# connect.net
KiCad netlist of a schematic drawn in Altium Designer
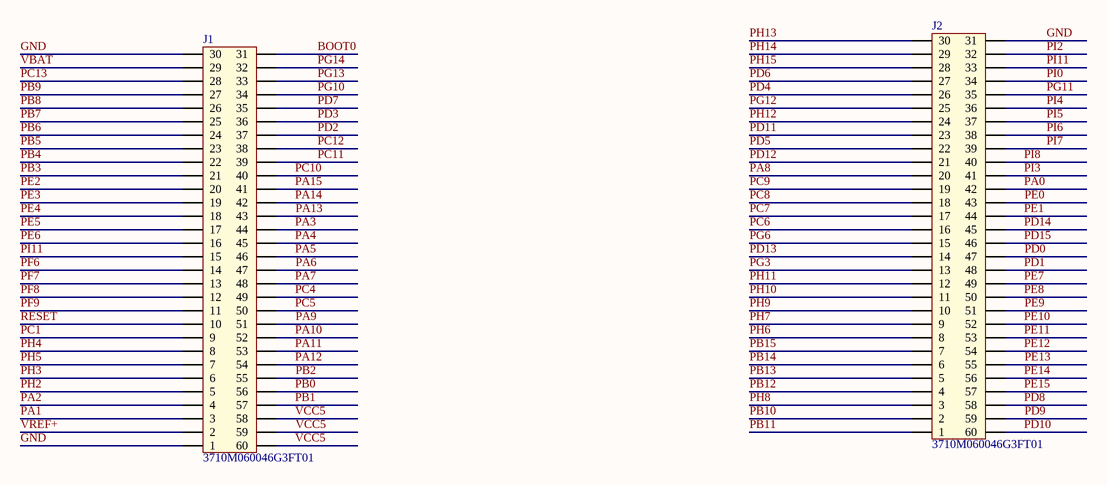
[diagram p0: connect.SchDoc]

(export (version "E")
  (design (tool "Eeschema 10.0.6"))
  (components
    (comp (ref "J1")
      (value "3710M060046G3FT01")
      (footprint "3710F060046G3FT01")
      (description "3710F060046G3FT01")
      (libsource (lib "STM32H743核心板封装库") (part "3710F"))
    )
    (comp (ref "J2")
      (value "3710M060046G3FT01")
      (footprint "3710F060046G3FT01")
      (description "3710F060046G3FT01")
      (libsource (lib "STM32H743核心板封装库") (part "3710F"))
    )
  )
  (nets
    (net (code "1") (name "/BOOT0") (class "Default")
      (node (ref "J1") (pin "31") (pinfunction "31_31") (pintype "passive"))
    )
    (net (code "2") (name "/GND") (class "Default")
      (node (ref "J1") (pin "1") (pinfunction "1_1") (pintype "passive"))
      (node (ref "J1") (pin "30") (pinfunction "30_30") (pintype "passive"))
      (node (ref "J2") (pin "31") (pinfunction "31_31") (pintype "passive"))
    )
    (net (code "3") (name "/PA0") (class "Default")
      (node (ref "J2") (pin "42") (pinfunction "42_42") (pintype "passive"))
    )
    (net (code "4") (name "/PA1") (class "Default")
      (node (ref "J1") (pin "3") (pinfunction "3_3") (pintype "passive"))
    )
    (net (code "5") (name "/PA2") (class "Default")
      (node (ref "J1") (pin "4") (pinfunction "4_4") (pintype "passive"))
    )
    (net (code "6") (name "/PA3") (class "Default")
      (node (ref "J1") (pin "44") (pinfunction "44_44") (pintype "passive"))
    )
    (net (code "7") (name "/PA4") (class "Default")
      (node (ref "J1") (pin "45") (pinfunction "45_45") (pintype "passive"))
    )
    (net (code "8") (name "/PA5") (class "Default")
      (node (ref "J1") (pin "46") (pinfunction "46_46") (pintype "passive"))
    )
    (net (code "9") (name "/PA6") (class "Default")
      (node (ref "J1") (pin "47") (pinfunction "47_47") (pintype "passive"))
    )
    (net (code "10") (name "/PA7") (class "Default")
      (node (ref "J1") (pin "48") (pinfunction "48_48") (pintype "passive"))
    )
    (net (code "11") (name "/PA8") (class "Default")
      (node (ref "J2") (pin "20") (pinfunction "20_20") (pintype "passive"))
    )
    (net (code "12") (name "/PA9") (class "Default")
      (node (ref "J1") (pin "51") (pinfunction "51_51") (pintype "passive"))
    )
    (net (code "13") (name "/PA10") (class "Default")
      (node (ref "J1") (pin "52") (pinfunction "52_52") (pintype "passive"))
    )
    (net (code "14") (name "/PA11") (class "Default")
      (node (ref "J1") (pin "53") (pinfunction "53_53") (pintype "passive"))
    )
    (net (code "15") (name "/PA12") (class "Default")
      (node (ref "J1") (pin "54") (pinfunction "54_54") (pintype "passive"))
    )
    (net (code "16") (name "/PA13") (class "Default")
      (node (ref "J1") (pin "43") (pinfunction "43_43") (pintype "passive"))
    )
    (net (code "17") (name "/PA14") (class "Default")
      (node (ref "J1") (pin "42") (pinfunction "42_42") (pintype "passive"))
    )
    (net (code "18") (name "/PA15") (class "Default")
      (node (ref "J1") (pin "41") (pinfunction "41_41") (pintype "passive"))
    )
    (net (code "19") (name "/PB0") (class "Default")
      (node (ref "J1") (pin "56") (pinfunction "56_56") (pintype "passive"))
    )
    (net (code "20") (name "/PB1") (class "Default")
      (node (ref "J1") (pin "57") (pinfunction "57_57") (pintype "passive"))
    )
    (net (code "21") (name "/PB2") (class "Default")
      (node (ref "J1") (pin "55") (pinfunction "55_55") (pintype "passive"))
    )
    (net (code "22") (name "/PB3") (class "Default")
      (node (ref "J1") (pin "21") (pinfunction "21_21") (pintype "passive"))
    )
    (net (code "23") (name "/PB4") (class "Default")
      (node (ref "J1") (pin "22") (pinfunction "22_22") (pintype "passive"))
    )
    (net (code "24") (name "/PB5") (class "Default")
      (node (ref "J1") (pin "23") (pinfunction "23_23") (pintype "passive"))
    )
    (net (code "25") (name "/PB6") (class "Default")
      (node (ref "J1") (pin "24") (pinfunction "24_24") (pintype "passive"))
    )
    (net (code "26") (name "/PB7") (class "Default")
      (node (ref "J1") (pin "25") (pinfunction "25_25") (pintype "passive"))
    )
    (net (code "27") (name "/PB8") (class "Default")
      (node (ref "J1") (pin "26") (pinfunction "26_26") (pintype "passive"))
    )
    (net (code "28") (name "/PB9") (class "Default")
      (node (ref "J1") (pin "27") (pinfunction "27_27") (pintype "passive"))
    )
    (net (code "29") (name "/PB10") (class "Default")
      (node (ref "J2") (pin "2") (pinfunction "2_2") (pintype "passive"))
    )
    (net (code "30") (name "/PB11") (class "Default")
      (node (ref "J2") (pin "1") (pinfunction "1_1") (pintype "passive"))
    )
    (net (code "31") (name "/PB12") (class "Default")
      (node (ref "J2") (pin "4") (pinfunction "4_4") (pintype "passive"))
    )
    (net (code "32") (name "/PB13") (class "Default")
      (node (ref "J2") (pin "5") (pinfunction "5_5") (pintype "passive"))
    )
    (net (code "33") (name "/PB14") (class "Default")
      (node (ref "J2") (pin "6") (pinfunction "6_6") (pintype "passive"))
    )
    (net (code "34") (name "/PB15") (class "Default")
      (node (ref "J2") (pin "7") (pinfunction "7_7") (pintype "passive"))
    )
    (net (code "35") (name "/PC1") (class "Default")
      (node (ref "J1") (pin "9") (pinfunction "9_9") (pintype "passive"))
    )
    (net (code "36") (name "/PC4") (class "Default")
      (node (ref "J1") (pin "49") (pinfunction "49_49") (pintype "passive"))
    )
    (net (code "37") (name "/PC5") (class "Default")
      (node (ref "J1") (pin "50") (pinfunction "50_50") (pintype "passive"))
    )
    (net (code "38") (name "/PC6") (class "Default")
      (node (ref "J2") (pin "16") (pinfunction "16_16") (pintype "passive"))
    )
    (net (code "39") (name "/PC7") (class "Default")
      (node (ref "J2") (pin "17") (pinfunction "17_17") (pintype "passive"))
    )
    (net (code "40") (name "/PC8") (class "Default")
      (node (ref "J2") (pin "18") (pinfunction "18_18") (pintype "passive"))
    )
    (net (code "41") (name "/PC9") (class "Default")
      (node (ref "J2") (pin "19") (pinfunction "19_19") (pintype "passive"))
    )
    (net (code "42") (name "/PC10") (class "Default")
      (node (ref "J1") (pin "40") (pinfunction "40_40") (pintype "passive"))
    )
    (net (code "43") (name "/PC11") (class "Default")
      (node (ref "J1") (pin "39") (pinfunction "39_39") (pintype "passive"))
    )
    (net (code "44") (name "/PC12") (class "Default")
      (node (ref "J1") (pin "38") (pinfunction "38_38") (pintype "passive"))
    )
    (net (code "45") (name "/PC13") (class "Default")
      (node (ref "J1") (pin "28") (pinfunction "28_28") (pintype "passive"))
    )
    (net (code "46") (name "/PD0") (class "Default")
      (node (ref "J2") (pin "47") (pinfunction "47_47") (pintype "passive"))
    )
    (net (code "47") (name "/PD1") (class "Default")
      (node (ref "J2") (pin "48") (pinfunction "48_48") (pintype "passive"))
    )
    (net (code "48") (name "/PD2") (class "Default")
      (node (ref "J1") (pin "37") (pinfunction "37_37") (pintype "passive"))
    )
    (net (code "49") (name "/PD3") (class "Default")
      (node (ref "J1") (pin "36") (pinfunction "36_36") (pintype "passive"))
    )
    (net (code "50") (name "/PD4") (class "Default")
      (node (ref "J2") (pin "26") (pinfunction "26_26") (pintype "passive"))
    )
    (net (code "51") (name "/PD5") (class "Default")
      (node (ref "J2") (pin "22") (pinfunction "22_22") (pintype "passive"))
    )
    (net (code "52") (name "/PD6") (class "Default")
      (node (ref "J2") (pin "27") (pinfunction "27_27") (pintype "passive"))
    )
    (net (code "53") (name "/PD7") (class "Default")
      (node (ref "J1") (pin "35") (pinfunction "35_35") (pintype "passive"))
    )
    (net (code "54") (name "/PD8") (class "Default")
      (node (ref "J2") (pin "58") (pinfunction "58_58") (pintype "passive"))
    )
    (net (code "55") (name "/PD9") (class "Default")
      (node (ref "J2") (pin "59") (pinfunction "59_59") (pintype "passive"))
    )
    (net (code "56") (name "/PD10") (class "Default")
      (node (ref "J2") (pin "60") (pinfunction "60_60") (pintype "passive"))
    )
    (net (code "57") (name "/PD11") (class "Default")
      (node (ref "J2") (pin "23") (pinfunction "23_23") (pintype "passive"))
    )
    (net (code "58") (name "/PD12") (class "Default")
      (node (ref "J2") (pin "21") (pinfunction "21_21") (pintype "passive"))
    )
    (net (code "59") (name "/PD13") (class "Default")
      (node (ref "J2") (pin "14") (pinfunction "14_14") (pintype "passive"))
    )
    (net (code "60") (name "/PD14") (class "Default")
      (node (ref "J2") (pin "45") (pinfunction "45_45") (pintype "passive"))
    )
    (net (code "61") (name "/PD15") (class "Default")
      (node (ref "J2") (pin "46") (pinfunction "46_46") (pintype "passive"))
    )
    (net (code "62") (name "/PE0") (class "Default")
      (node (ref "J2") (pin "43") (pinfunction "43_43") (pintype "passive"))
    )
    (net (code "63") (name "/PE1") (class "Default")
      (node (ref "J2") (pin "44") (pinfunction "44_44") (pintype "passive"))
    )
    (net (code "64") (name "/PE2") (class "Default")
      (node (ref "J1") (pin "20") (pinfunction "20_20") (pintype "passive"))
    )
    (net (code "65") (name "/PE3") (class "Default")
      (node (ref "J1") (pin "19") (pinfunction "19_19") (pintype "passive"))
    )
    (net (code "66") (name "/PE4") (class "Default")
      (node (ref "J1") (pin "18") (pinfunction "18_18") (pintype "passive"))
    )
    (net (code "67") (name "/PE5") (class "Default")
      (node (ref "J1") (pin "17") (pinfunction "17_17") (pintype "passive"))
    )
    (net (code "68") (name "/PE6") (class "Default")
      (node (ref "J1") (pin "16") (pinfunction "16_16") (pintype "passive"))
    )
    (net (code "69") (name "/PE7") (class "Default")
      (node (ref "J2") (pin "49") (pinfunction "49_49") (pintype "passive"))
    )
    (net (code "70") (name "/PE8") (class "Default")
      (node (ref "J2") (pin "50") (pinfunction "50_50") (pintype "passive"))
    )
    (net (code "71") (name "/PE9") (class "Default")
      (node (ref "J2") (pin "51") (pinfunction "51_51") (pintype "passive"))
    )
    (net (code "72") (name "/PE10") (class "Default")
      (node (ref "J2") (pin "52") (pinfunction "52_52") (pintype "passive"))
    )
    (net (code "73") (name "/PE11") (class "Default")
      (node (ref "J2") (pin "53") (pinfunction "53_53") (pintype "passive"))
    )
    (net (code "74") (name "/PE12") (class "Default")
      (node (ref "J2") (pin "54") (pinfunction "54_54") (pintype "passive"))
    )
    (net (code "75") (name "/PE13") (class "Default")
      (node (ref "J2") (pin "55") (pinfunction "55_55") (pintype "passive"))
    )
    (net (code "76") (name "/PE14") (class "Default")
      (node (ref "J2") (pin "56") (pinfunction "56_56") (pintype "passive"))
    )
    (net (code "77") (name "/PE15") (class "Default")
      (node (ref "J2") (pin "57") (pinfunction "57_57") (pintype "passive"))
    )
    (net (code "78") (name "/PF6") (class "Default")
      (node (ref "J1") (pin "14") (pinfunction "14_14") (pintype "passive"))
    )
    (net (code "79") (name "/PF7") (class "Default")
      (node (ref "J1") (pin "13") (pinfunction "13_13") (pintype "passive"))
    )
    (net (code "80") (name "/PF8") (class "Default")
      (node (ref "J1") (pin "12") (pinfunction "12_12") (pintype "passive"))
    )
    (net (code "81") (name "/PF9") (class "Default")
      (node (ref "J1") (pin "11") (pinfunction "11_11") (pintype "passive"))
    )
    (net (code "82") (name "/PG3") (class "Default")
      (node (ref "J2") (pin "13") (pinfunction "13_13") (pintype "passive"))
    )
    (net (code "83") (name "/PG6") (class "Default")
      (node (ref "J2") (pin "15") (pinfunction "15_15") (pintype "passive"))
    )
    (net (code "84") (name "/PG10") (class "Default")
      (node (ref "J1") (pin "34") (pinfunction "34_34") (pintype "passive"))
    )
    (net (code "85") (name "/PG11") (class "Default")
      (node (ref "J2") (pin "35") (pinfunction "35_35") (pintype "passive"))
    )
    (net (code "86") (name "/PG12") (class "Default")
      (node (ref "J2") (pin "25") (pinfunction "25_25") (pintype "passive"))
    )
    (net (code "87") (name "/PG13") (class "Default")
      (node (ref "J1") (pin "33") (pinfunction "33_33") (pintype "passive"))
    )
    (net (code "88") (name "/PG14") (class "Default")
      (node (ref "J1") (pin "32") (pinfunction "32_32") (pintype "passive"))
    )
    (net (code "89") (name "/PH2") (class "Default")
      (node (ref "J1") (pin "5") (pinfunction "5_5") (pintype "passive"))
    )
    (net (code "90") (name "/PH3") (class "Default")
      (node (ref "J1") (pin "6") (pinfunction "6_6") (pintype "passive"))
    )
    (net (code "91") (name "/PH4") (class "Default")
      (node (ref "J1") (pin "8") (pinfunction "8_8") (pintype "passive"))
    )
    (net (code "92") (name "/PH5") (class "Default")
      (node (ref "J1") (pin "7") (pinfunction "7_7") (pintype "passive"))
    )
    (net (code "93") (name "/PH6") (class "Default")
      (node (ref "J2") (pin "8") (pinfunction "8_8") (pintype "passive"))
    )
    (net (code "94") (name "/PH7") (class "Default")
      (node (ref "J2") (pin "9") (pinfunction "9_9") (pintype "passive"))
    )
    (net (code "95") (name "/PH8") (class "Default")
      (node (ref "J2") (pin "3") (pinfunction "3_3") (pintype "passive"))
    )
    (net (code "96") (name "/PH9") (class "Default")
      (node (ref "J2") (pin "10") (pinfunction "10_10") (pintype "passive"))
    )
    (net (code "97") (name "/PH10") (class "Default")
      (node (ref "J2") (pin "11") (pinfunction "11_11") (pintype "passive"))
    )
    (net (code "98") (name "/PH11") (class "Default")
      (node (ref "J2") (pin "12") (pinfunction "12_12") (pintype "passive"))
    )
    (net (code "99") (name "/PH12") (class "Default")
      (node (ref "J2") (pin "24") (pinfunction "24_24") (pintype "passive"))
    )
    (net (code "100") (name "/PH13") (class "Default")
      (node (ref "J2") (pin "30") (pinfunction "30_30") (pintype "passive"))
    )
    (net (code "101") (name "/PH14") (class "Default")
      (node (ref "J2") (pin "29") (pinfunction "29_29") (pintype "passive"))
    )
    (net (code "102") (name "/PH15") (class "Default")
      (node (ref "J2") (pin "28") (pinfunction "28_28") (pintype "passive"))
    )
    (net (code "103") (name "/PI0") (class "Default")
      (node (ref "J2") (pin "34") (pinfunction "34_34") (pintype "passive"))
    )
    (net (code "104") (name "/PI2") (class "Default")
      (node (ref "J2") (pin "32") (pinfunction "32_32") (pintype "passive"))
    )
    (net (code "105") (name "/PI3") (class "Default")
      (node (ref "J2") (pin "41") (pinfunction "41_41") (pintype "passive"))
    )
    (net (code "106") (name "/PI4") (class "Default")
      (node (ref "J2") (pin "36") (pinfunction "36_36") (pintype "passive"))
    )
    (net (code "107") (name "/PI5") (class "Default")
      (node (ref "J2") (pin "37") (pinfunction "37_37") (pintype "passive"))
    )
    (net (code "108") (name "/PI6") (class "Default")
      (node (ref "J2") (pin "38") (pinfunction "38_38") (pintype "passive"))
    )
    (net (code "109") (name "/PI7") (class "Default")
      (node (ref "J2") (pin "39") (pinfunction "39_39") (pintype "passive"))
    )
    (net (code "110") (name "/PI8") (class "Default")
      (node (ref "J2") (pin "40") (pinfunction "40_40") (pintype "passive"))
    )
    (net (code "111") (name "/PI11") (class "Default")
      (node (ref "J1") (pin "15") (pinfunction "15_15") (pintype "passive"))
      (node (ref "J2") (pin "33") (pinfunction "33_33") (pintype "passive"))
    )
    (net (code "112") (name "/RESET") (class "Default")
      (node (ref "J1") (pin "10") (pinfunction "10_10") (pintype "passive"))
    )
    (net (code "113") (name "/VBAT") (class "Default")
      (node (ref "J1") (pin "29") (pinfunction "29_29") (pintype "passive"))
    )
    (net (code "114") (name "/VCC5") (class "Default")
      (node (ref "J1") (pin "58") (pinfunction "58_58") (pintype "passive"))
      (node (ref "J1") (pin "59") (pinfunction "59_59") (pintype "passive"))
      (node (ref "J1") (pin "60") (pinfunction "60_60") (pintype "passive"))
    )
    (net (code "115") (name "/VREF+") (class "Default")
      (node (ref "J1") (pin "2") (pinfunction "2_2") (pintype "passive"))
    )
  )
)
